# Mains.net
KiCad netlist of a schematic drawn in Altium Designer
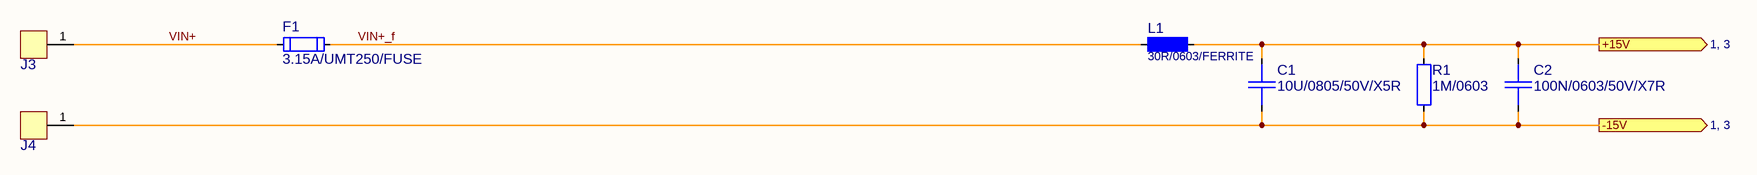
[diagram p0: Mains.SchDoc]

(export (version "E")
  (design (tool "Eeschema 10.0.6"))
  (components
    (comp (ref "C1")
      (value "10U/0805/50V/X5R")
      (footprint "CAP0805_X7R")
      (description "CAP SM 0805 10uF 50V X5R")
      (fields (field (name "MANUFACTURER") "GENERIC"))
      (libsource (lib "daniw_altium_lib") (part "C"))
    )
    (comp (ref "C2")
      (value "100N/0603/50V/X7R")
      (footprint "CAP0603_X7R")
      (description "CAP SM 0603 100nF 50V X7R")
      (fields (field (name "MANUFACTURER") "GENERIC"))
      (libsource (lib "daniw_altium_lib") (part "C"))
    )
    (comp (ref "F1")
      (value "3.15A/UMT250/FUSE")
      (footprint "UMT250")
      (description "Fuse 250VAC 3.15A UMT250")
      (fields (field (name "MANUFACTURER") "Schurter"))
      (libsource (lib "daniw_altium_lib") (part "Fuse"))
    )
    (comp (ref "J3")
      (value "6.35mmx0.81mm Tab THT")
      (footprint "Tab_THT_635")
      (description "CONN QC TAB 0.250 SOLDER")
      (fields (field (name "PART NUMBER") "Tab_025_THT") (field (name "MANUFACTURER") "GENERIC"))
      (libsource (lib "daniw_altium_lib") (part "CON1"))
    )
    (comp (ref "J4")
      (value "6.35mmx0.81mm Tab THT")
      (footprint "Tab_THT_635")
      (description "CONN QC TAB 0.250 SOLDER")
      (fields (field (name "PART NUMBER") "Tab_025_THT") (field (name "MANUFACTURER") "GENERIC"))
      (libsource (lib "daniw_altium_lib") (part "CON1"))
    )
    (comp (ref "L1")
      (value "30R/0603/FERRITE")
      (footprint "FB0603")
      (description "30R@100MHz 5A 0603 Ferrite")
      (fields (field (name "MANUFACTURER") "GENERIC"))
      (libsource (lib "daniw_altium_lib") (part "Ferrite"))
    )
    (comp (ref "R1")
      (value "1M/0603")
      (footprint "R0603-0.40-WW")
      (description "RES SM 0603 1M")
      (fields (field (name "MANUFACTURER") "GENERIC"))
      (libsource (lib "daniw_altium_lib") (part "R"))
    )
  )
  (nets
    (net (code "1") (name "/+15V") (class "Default")
      (node (ref "C1") (pin "1") (pinfunction "1_1") (pintype "passive"))
      (node (ref "C2") (pin "1") (pinfunction "1_1") (pintype "passive"))
      (node (ref "L1") (pin "2") (pinfunction "2_2") (pintype "passive"))
      (node (ref "R1") (pin "1") (pinfunction "1_1") (pintype "passive"))
    )
    (net (code "2") (name "/-15V") (class "Default")
      (node (ref "C1") (pin "2") (pinfunction "2_2") (pintype "passive"))
      (node (ref "C2") (pin "2") (pinfunction "2_2") (pintype "passive"))
      (node (ref "J4") (pin "1") (pintype "passive"))
      (node (ref "R1") (pin "2") (pinfunction "2_2") (pintype "passive"))
    )
    (net (code "3") (name "/VIN+") (class "Default")
      (node (ref "F1") (pin "1") (pinfunction "1_1") (pintype "passive"))
      (node (ref "J3") (pin "1") (pintype "passive"))
    )
    (net (code "4") (name "/VIN+_f") (class "Default")
      (node (ref "F1") (pin "2") (pinfunction "2_2") (pintype "passive"))
      (node (ref "L1") (pin "1") (pinfunction "1_1") (pintype "passive"))
    )
  )
)
